# Fonte3V3.net
KiCad netlist of a schematic drawn in Altium Designer
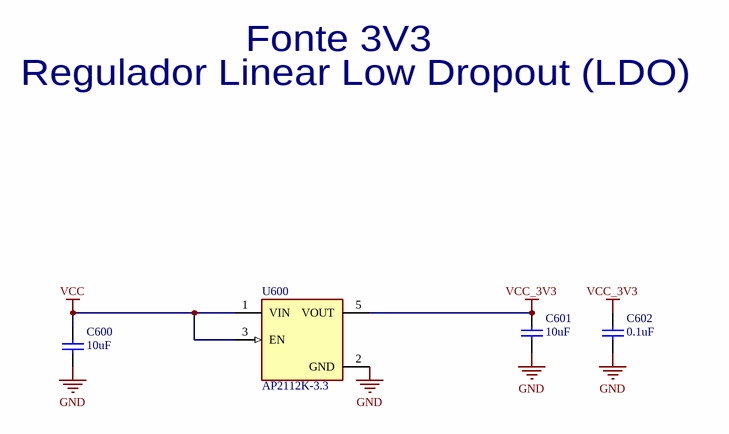
[diagram p0: Fonte3V3.SchDoc]

(export (version "E")
  (design (tool "Eeschema 10.0.6"))
  (components
    (comp (ref "C600")
      (value "10uF")
      (footprint "CAP_CER_0805")
      (libsource (lib "PCB_TCC") (part "CAP_CER_10uF_0805"))
    )
    (comp (ref "C601")
      (value "10uF")
      (footprint "CAP_CER_0805")
      (libsource (lib "PCB_TCC") (part "CAP_CER_10uF_0805"))
    )
    (comp (ref "C602")
      (value "0.1uF")
      (footprint "CAP_CER_0603")
      (libsource (lib "PCB_TCC") (part "CAP_CER_0.1uF_0603"))
    )
    (comp (ref "U600")
      (value "AP2112K-3.3")
      (footprint "AP2112K-3.3")
      (libsource (lib "PCB_TCC") (part "AP2112K-3.3"))
    )
  )
  (nets
    (net (code "1") (name "GND") (class "Default")
      (node (ref "C600") (pin "2") (pinfunction "2_2") (pintype "passive"))
      (node (ref "C601") (pin "2") (pinfunction "2_2") (pintype "passive"))
      (node (ref "C602") (pin "1") (pinfunction "1_1") (pintype "passive"))
      (node (ref "U600") (pin "2") (pinfunction "GND_2") (pintype "power_in"))
    )
    (net (code "2") (name "VCC") (class "Default")
      (node (ref "C600") (pin "1") (pinfunction "1_1") (pintype "passive"))
      (node (ref "U600") (pin "1") (pinfunction "VIN_1") (pintype "power_in"))
      (node (ref "U600") (pin "3") (pinfunction "EN_3") (pintype "input"))
    )
    (net (code "3") (name "VCC_3V3") (class "Default")
      (node (ref "C601") (pin "1") (pinfunction "1_1") (pintype "passive"))
      (node (ref "C602") (pin "2") (pinfunction "2_2") (pintype "passive"))
      (node (ref "U600") (pin "5") (pinfunction "VOUT_5") (pintype "power_in"))
    )
  )
)
